# TUDSSL_condenar__Hardware_PCBs_Misc_Apo4.net
KiCad netlist of a schematic drawn in Altium Designer
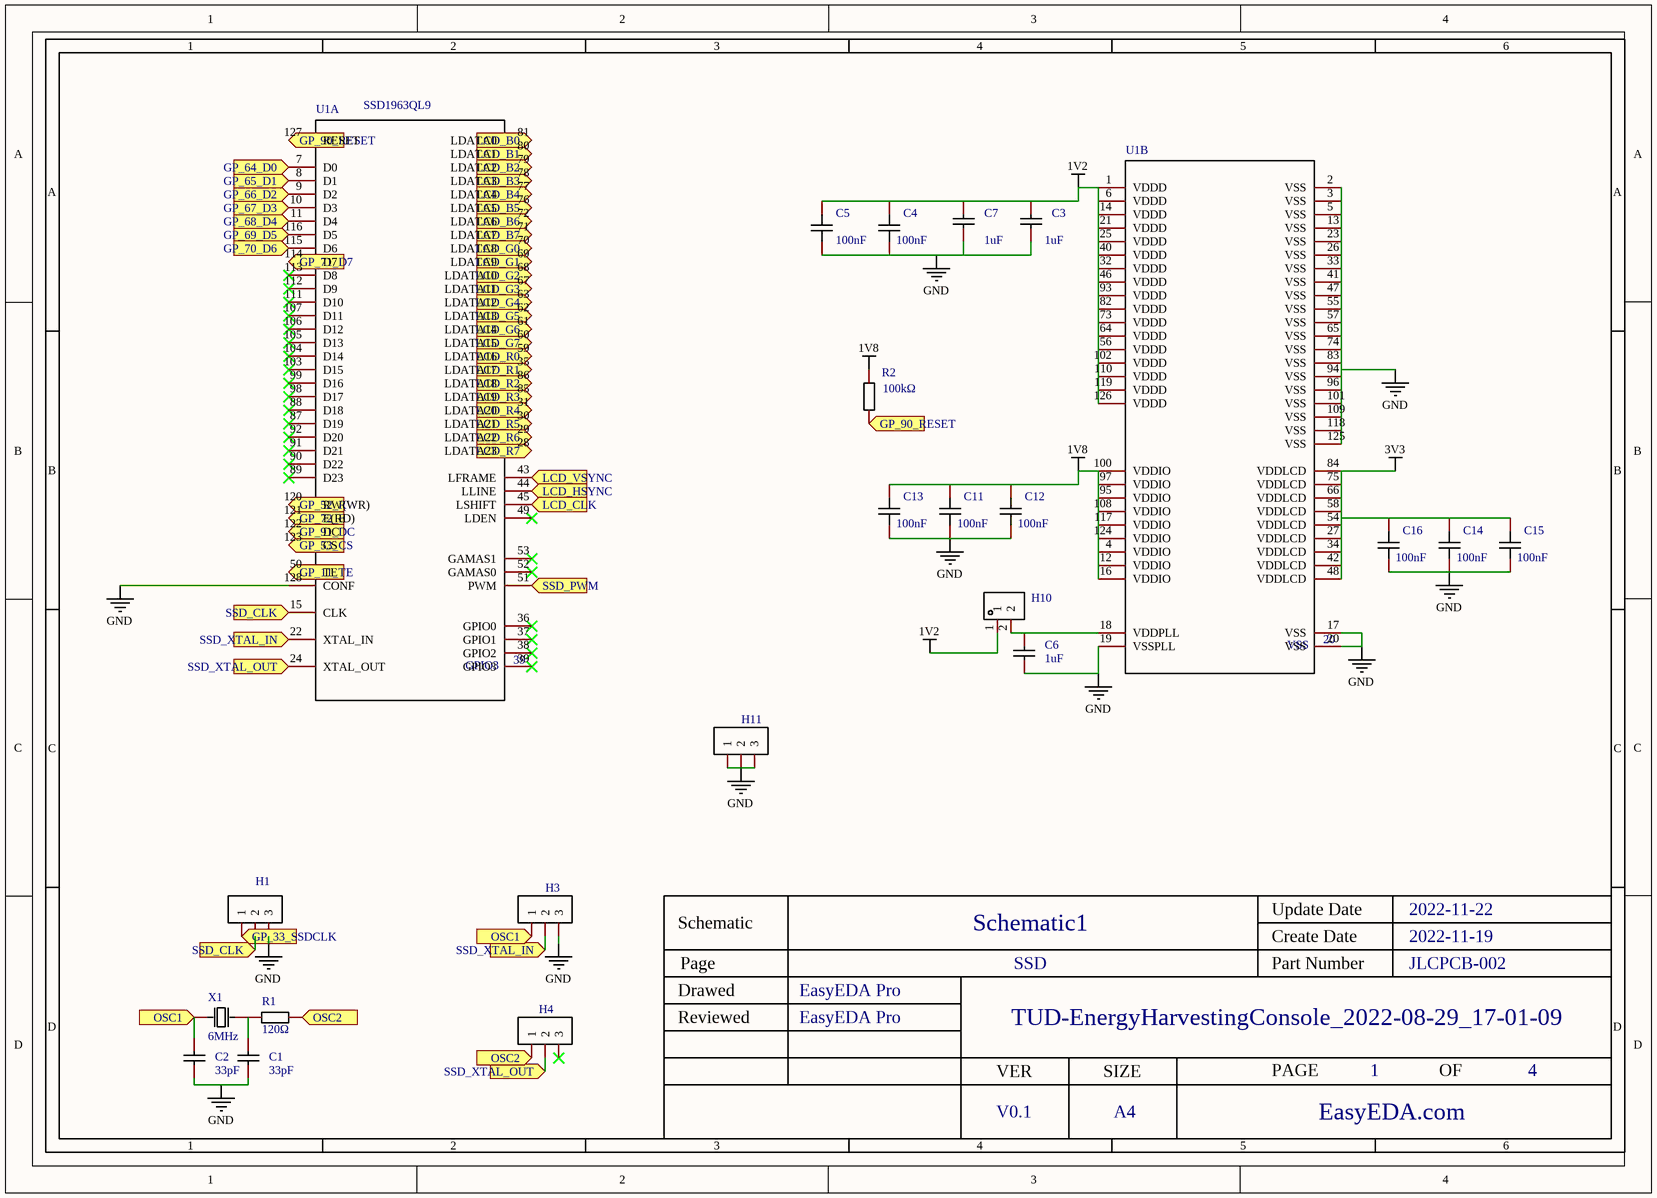
[diagram p0: TUDSSL_condenar__Hardware_PCBs_Misc_Apo4devkit2COM50_Schematic1__4_SSD.schdoc]

(export (version "E")
  (design (tool "Eeschema 10.0.6"))
  (components
    (comp (ref "C1")
      (value "33pF")
      (fields
        (field (name "MANUFACTURER") "YAGEO(国巨)")
        (field (name "MANUFACTURER PART") "CC0805JRNPO9BN330")
        (field (name "TOLERANCE") "±5%")
      )
      (libsource (lib "altium-import") (part "root_1_CC0805JRNPO9BN330_"))
    )
    (comp (ref "C2")
      (value "33pF")
      (fields
        (field (name "MANUFACTURER") "YAGEO(国巨)")
        (field (name "MANUFACTURER PART") "CC0805JRNPO9BN330")
        (field (name "TOLERANCE") "±5%")
      )
      (libsource (lib "altium-import") (part "root_1_CC0805JRNPO9BN330_"))
    )
    (comp (ref "C3")
      (value "1uF")
      (fields
        (field (name "MANUFACTURER") "SAMSUNG(三星)")
        (field (name "MANUFACTURER PART") "CL10A105KB8NNNC")
      )
      (libsource (lib "altium-import") (part "root_1_CL10A105KB8NNNC_"))
    )
    (comp (ref "C4")
      (value "100nF")
      (fields
        (field (name "MANUFACTURER") "YAGEO(国巨)")
        (field (name "MANUFACTURER PART") "CC0603KRX7R9BB104")
        (field (name "TOLERANCE") "±10%")
      )
      (libsource (lib "altium-import") (part "root_1_CC0603KRX7R9BB104_"))
    )
    (comp (ref "C5")
      (value "100nF")
      (fields
        (field (name "MANUFACTURER") "YAGEO(国巨)")
        (field (name "MANUFACTURER PART") "CC0603KRX7R9BB104")
        (field (name "TOLERANCE") "±10%")
      )
      (libsource (lib "altium-import") (part "root_1_CC0603KRX7R9BB104_"))
    )
    (comp (ref "C6")
      (value "1uF")
      (fields
        (field (name "MANUFACTURER") "SAMSUNG(三星)")
        (field (name "MANUFACTURER PART") "CL10A105KB8NNNC")
      )
      (libsource (lib "altium-import") (part "root_1_CL10A105KB8NNNC_"))
    )
    (comp (ref "C7")
      (value "1uF")
      (fields
        (field (name "MANUFACTURER") "SAMSUNG(三星)")
        (field (name "MANUFACTURER PART") "CL10A105KB8NNNC")
      )
      (libsource (lib "altium-import") (part "root_1_CL10A105KB8NNNC_"))
    )
    (comp (ref "C11")
      (value "100nF")
      (fields
        (field (name "MANUFACTURER") "YAGEO(国巨)")
        (field (name "MANUFACTURER PART") "CC0603KRX7R9BB104")
        (field (name "TOLERANCE") "±10%")
      )
      (libsource (lib "altium-import") (part "root_1_CC0603KRX7R9BB104_"))
    )
    (comp (ref "C12")
      (value "100nF")
      (fields
        (field (name "MANUFACTURER") "YAGEO(国巨)")
        (field (name "MANUFACTURER PART") "CC0603KRX7R9BB104")
        (field (name "TOLERANCE") "±10%")
      )
      (libsource (lib "altium-import") (part "root_1_CC0603KRX7R9BB104_"))
    )
    (comp (ref "C13")
      (value "100nF")
      (fields
        (field (name "MANUFACTURER") "YAGEO(国巨)")
        (field (name "MANUFACTURER PART") "CC0603KRX7R9BB104")
        (field (name "TOLERANCE") "±10%")
      )
      (libsource (lib "altium-import") (part "root_1_CC0603KRX7R9BB104_"))
    )
    (comp (ref "C14")
      (value "100nF")
      (fields
        (field (name "MANUFACTURER") "YAGEO(国巨)")
        (field (name "MANUFACTURER PART") "CC0603KRX7R9BB104")
        (field (name "TOLERANCE") "±10%")
      )
      (libsource (lib "altium-import") (part "root_1_CC0603KRX7R9BB104_"))
    )
    (comp (ref "C15")
      (value "100nF")
      (fields
        (field (name "MANUFACTURER") "YAGEO(国巨)")
        (field (name "MANUFACTURER PART") "CC0603KRX7R9BB104")
        (field (name "TOLERANCE") "±10%")
      )
      (libsource (lib "altium-import") (part "root_1_CC0603KRX7R9BB104_"))
    )
    (comp (ref "C16")
      (value "100nF")
      (fields
        (field (name "MANUFACTURER") "YAGEO(国巨)")
        (field (name "MANUFACTURER PART") "CC0603KRX7R9BB104")
        (field (name "TOLERANCE") "±10%")
      )
      (libsource (lib "altium-import") (part "root_1_CC0603KRX7R9BB104_"))
    )
    (comp (ref "H1")
      (value "2.54-1*3P针")
      (fields (field (name "MANUFACTURER") "BOOMELE(博穆精密)"))
      (libsource (lib "altium-import") (part "root_1_2.54-1*3P针_"))
    )
    (comp (ref "H3")
      (value "2.54-1*3P针")
      (fields (field (name "MANUFACTURER") "BOOMELE(博穆精密)"))
      (libsource (lib "altium-import") (part "root_1_2.54-1*3P针_"))
    )
    (comp (ref "H4")
      (value "2.54-1*3P针")
      (fields (field (name "MANUFACTURER") "BOOMELE(博穆精密)"))
      (libsource (lib "altium-import") (part "root_1_2.54-1*3P针_"))
    )
    (comp (ref "H10")
      (value "PZ254V-11-02P")
      (fields (field (name "MANUFACTURER") "XFCN(兴飞)"))
      (libsource (lib "altium-import") (part "root_1_PZ254V-11-02P_"))
    )
    (comp (ref "H11")
      (value "2.54-1*3P针")
      (fields (field (name "MANUFACTURER") "BOOMELE(博穆精密)"))
      (libsource (lib "altium-import") (part "root_1_2.54-1*3P针_"))
    )
    (comp (ref "R1")
      (value "120Ω")
      (fields
        (field (name "MANUFACTURER") "UNI-ROYAL(厚声)")
        (field (name "MANUFACTURER PART") "0603WAF1200T5E")
        (field (name "TOLERANCE") "±1%")
      )
      (libsource (lib "altium-import") (part "root_0_0603WAF1200T5E_"))
    )
    (comp (ref "R2")
      (value "100kΩ")
      (fields
        (field (name "MANUFACTURER") "UNI-ROYAL(厚声)")
        (field (name "MANUFACTURER PART") "0603WAF1003T5E")
        (field (name "TOLERANCE") "±1%")
      )
      (libsource (lib "altium-import") (part "root_1_0603WAF1003T5E_"))
    )
    (comp (ref "U1")
      (value "SSD1963QL9")
      (fields
        (field (name "MANUFACTURER") "SOLOMON(晶门科技)")
        (field (name "NAME") "VSS")
        (field (name "NUMBER") "20")
        (field (name "LCSC PART NAME") "SSD1963QL9")
      )
      (libsource (lib "altium-import") (part "root_0_SSD1963QL9_"))
    )
    (comp (ref "X1")
      (value "6MHz")
      (fields (field (name "MANUFACTURER") "SJK(晶科鑫)") (field (name "MANUFACTURER PART") "6CS06000F20UCG"))
      (libsource (lib "altium-import") (part "root_0_6CS06000F20UCG_"))
    )
  )
  (nets
    (net (code "1") (name "/GP_11_TE") (class "Default")
      (node (ref "U1") (pin "50") (pinfunction "TE_50") (pintype "passive"))
    )
    (net (code "2") (name "/GP_33_SSDCLK") (class "Default")
      (node (ref "H1") (pin "1") (pinfunction "1_1") (pintype "passive"))
    )
    (net (code "3") (name "/GP_52_RW") (class "Default")
      (node (ref "U1") (pin "120") (pinfunction "RW(WR)_120") (pintype "passive"))
    )
    (net (code "4") (name "/GP_53_CS") (class "Default")
      (node (ref "U1") (pin "123") (pinfunction "CS_123") (pintype "passive"))
    )
    (net (code "5") (name "/GP_64_D0") (class "Default")
      (node (ref "U1") (pin "7") (pinfunction "D0_7") (pintype "passive"))
    )
    (net (code "6") (name "/GP_65_D1") (class "Default")
      (node (ref "U1") (pin "8") (pinfunction "D1_8") (pintype "passive"))
    )
    (net (code "7") (name "/GP_66_D2") (class "Default")
      (node (ref "U1") (pin "9") (pinfunction "D2_9") (pintype "passive"))
    )
    (net (code "8") (name "/GP_67_D3") (class "Default")
      (node (ref "U1") (pin "10") (pinfunction "D3_10") (pintype "passive"))
    )
    (net (code "9") (name "/GP_68_D4") (class "Default")
      (node (ref "U1") (pin "11") (pinfunction "D4_11") (pintype "passive"))
    )
    (net (code "10") (name "/GP_69_D5") (class "Default")
      (node (ref "U1") (pin "116") (pinfunction "D5_116") (pintype "passive"))
    )
    (net (code "11") (name "/GP_70_D6") (class "Default")
      (node (ref "U1") (pin "115") (pinfunction "D6_115") (pintype "passive"))
    )
    (net (code "12") (name "/GP_71_D7") (class "Default")
      (node (ref "U1") (pin "114") (pinfunction "D7_114") (pintype "passive"))
    )
    (net (code "13") (name "/GP_72_E") (class "Default")
      (node (ref "U1") (pin "121") (pinfunction "E(RD)_121") (pintype "passive"))
    )
    (net (code "14") (name "/GP_90_RESET") (class "Default")
      (node (ref "R2") (pin "1") (pinfunction "1_1") (pintype "passive"))
      (node (ref "U1") (pin "127") (pinfunction "RESET_127") (pintype "passive"))
    )
    (net (code "15") (name "/GP_91_DC") (class "Default")
      (node (ref "U1") (pin "122") (pinfunction "DC_122") (pintype "passive"))
    )
    (net (code "16") (name "/LCD_B0") (class "Default")
      (node (ref "U1") (pin "81") (pinfunction "LDATA0_81") (pintype "passive"))
    )
    (net (code "17") (name "/LCD_B1") (class "Default")
      (node (ref "U1") (pin "80") (pinfunction "LDATA1_80") (pintype "passive"))
    )
    (net (code "18") (name "/LCD_B2") (class "Default")
      (node (ref "U1") (pin "79") (pinfunction "LDATA2_79") (pintype "passive"))
    )
    (net (code "19") (name "/LCD_B3") (class "Default")
      (node (ref "U1") (pin "78") (pinfunction "LDATA3_78") (pintype "passive"))
    )
    (net (code "20") (name "/LCD_B4") (class "Default")
      (node (ref "U1") (pin "77") (pinfunction "LDATA4_77") (pintype "passive"))
    )
    (net (code "21") (name "/LCD_B5") (class "Default")
      (node (ref "U1") (pin "76") (pinfunction "LDATA5_76") (pintype "passive"))
    )
    (net (code "22") (name "/LCD_B6") (class "Default")
      (node (ref "U1") (pin "72") (pinfunction "LDATA6_72") (pintype "passive"))
    )
    (net (code "23") (name "/LCD_B7") (class "Default")
      (node (ref "U1") (pin "71") (pinfunction "LDATA7_71") (pintype "passive"))
    )
    (net (code "24") (name "/LCD_CLK") (class "Default")
      (node (ref "U1") (pin "45") (pinfunction "LSHIFT_45") (pintype "passive"))
    )
    (net (code "25") (name "/LCD_G0") (class "Default")
      (node (ref "U1") (pin "70") (pinfunction "LDATA8_70") (pintype "passive"))
    )
    (net (code "26") (name "/LCD_G1") (class "Default")
      (node (ref "U1") (pin "69") (pinfunction "LDATA9_69") (pintype "passive"))
    )
    (net (code "27") (name "/LCD_G2") (class "Default")
      (node (ref "U1") (pin "68") (pinfunction "LDATA10_68") (pintype "passive"))
    )
    (net (code "28") (name "/LCD_G3") (class "Default")
      (node (ref "U1") (pin "67") (pinfunction "LDATA11_67") (pintype "passive"))
    )
    (net (code "29") (name "/LCD_G4") (class "Default")
      (node (ref "U1") (pin "63") (pinfunction "LDATA12_63") (pintype "passive"))
    )
    (net (code "30") (name "/LCD_G5") (class "Default")
      (node (ref "U1") (pin "62") (pinfunction "LDATA13_62") (pintype "passive"))
    )
    (net (code "31") (name "/LCD_G6") (class "Default")
      (node (ref "U1") (pin "61") (pinfunction "LDATA14_61") (pintype "passive"))
    )
    (net (code "32") (name "/LCD_G7") (class "Default")
      (node (ref "U1") (pin "60") (pinfunction "LDATA15_60") (pintype "passive"))
    )
    (net (code "33") (name "/LCD_HSYNC") (class "Default")
      (node (ref "U1") (pin "44") (pinfunction "LLINE_44") (pintype "passive"))
    )
    (net (code "34") (name "/LCD_R0") (class "Default")
      (node (ref "U1") (pin "59") (pinfunction "LDATA16_59") (pintype "passive"))
    )
    (net (code "35") (name "/LCD_R1") (class "Default")
      (node (ref "U1") (pin "35") (pinfunction "LDATA17_35") (pintype "passive"))
    )
    (net (code "36") (name "/LCD_R2") (class "Default")
      (node (ref "U1") (pin "86") (pinfunction "LDATA18_86") (pintype "passive"))
    )
    (net (code "37") (name "/LCD_R3") (class "Default")
      (node (ref "U1") (pin "85") (pinfunction "LDATA19_85") (pintype "passive"))
    )
    (net (code "38") (name "/LCD_R4") (class "Default")
      (node (ref "U1") (pin "31") (pinfunction "LDATA20_31") (pintype "passive"))
    )
    (net (code "39") (name "/LCD_R5") (class "Default")
      (node (ref "U1") (pin "30") (pinfunction "LDATA21_30") (pintype "passive"))
    )
    (net (code "40") (name "/LCD_R6") (class "Default")
      (node (ref "U1") (pin "29") (pinfunction "LDATA22_29") (pintype "passive"))
    )
    (net (code "41") (name "/LCD_R7") (class "Default")
      (node (ref "U1") (pin "28") (pinfunction "LDATA23_28") (pintype "passive"))
    )
    (net (code "42") (name "/LCD_VSYNC") (class "Default")
      (node (ref "U1") (pin "43") (pinfunction "LFRAME_43") (pintype "passive"))
    )
    (net (code "43") (name "/OSC1") (class "Default")
      (node (ref "C2") (pin "2") (pinfunction "2_2") (pintype "passive"))
      (node (ref "H3") (pin "1") (pinfunction "1_1") (pintype "passive"))
      (node (ref "X1") (pin "1") (pinfunction "OSC1_1") (pintype "passive"))
    )
    (net (code "44") (name "/OSC2") (class "Default")
      (node (ref "H4") (pin "1") (pinfunction "1_1") (pintype "passive"))
      (node (ref "R1") (pin "2") (pinfunction "2_2") (pintype "passive"))
    )
    (net (code "45") (name "/SSD_CLK") (class "Default")
      (node (ref "H1") (pin "2") (pinfunction "2_2") (pintype "passive"))
      (node (ref "U1") (pin "15") (pinfunction "CLK_15") (pintype "passive"))
    )
    (net (code "46") (name "/SSD_PWM") (class "Default")
      (node (ref "U1") (pin "51") (pinfunction "PWM_51") (pintype "passive"))
    )
    (net (code "47") (name "/SSD_XTAL_IN") (class "Default")
      (node (ref "H3") (pin "2") (pinfunction "2_2") (pintype "passive"))
      (node (ref "U1") (pin "22") (pinfunction "XTAL_IN_22") (pintype "passive"))
    )
    (net (code "48") (name "/SSD_XTAL_OUT") (class "Default")
      (node (ref "H4") (pin "2") (pinfunction "2_2") (pintype "passive"))
      (node (ref "U1") (pin "24") (pinfunction "XTAL_OUT_24") (pintype "passive"))
    )
    (net (code "49") (name "1V2") (class "Default")
      (node (ref "C3") (pin "2") (pinfunction "2_2") (pintype "passive"))
      (node (ref "C4") (pin "2") (pinfunction "2_2") (pintype "passive"))
      (node (ref "C5") (pin "2") (pinfunction "2_2") (pintype "passive"))
      (node (ref "C7") (pin "2") (pinfunction "2_2") (pintype "passive"))
      (node (ref "H10") (pin "1") (pinfunction "1_1") (pintype "passive"))
      (node (ref "U1") (pin "1") (pinfunction "VDDD_1") (pintype "passive"))
      (node (ref "U1") (pin "102") (pinfunction "VDDD_102") (pintype "passive"))
      (node (ref "U1") (pin "110") (pinfunction "VDDD_110") (pintype "passive"))
      (node (ref "U1") (pin "119") (pinfunction "VDDD_119") (pintype "passive"))
      (node (ref "U1") (pin "126") (pinfunction "VDDD_126") (pintype "passive"))
      (node (ref "U1") (pin "14") (pinfunction "VDDD_14") (pintype "passive"))
      (node (ref "U1") (pin "21") (pinfunction "VDDD_21") (pintype "passive"))
      (node (ref "U1") (pin "25") (pinfunction "VDDD_25") (pintype "passive"))
      (node (ref "U1") (pin "32") (pinfunction "VDDD_32") (pintype "passive"))
      (node (ref "U1") (pin "40") (pinfunction "VDDD_40") (pintype "passive"))
      (node (ref "U1") (pin "46") (pinfunction "VDDD_46") (pintype "passive"))
      (node (ref "U1") (pin "56") (pinfunction "VDDD_56") (pintype "passive"))
      (node (ref "U1") (pin "6") (pinfunction "VDDD_6") (pintype "passive"))
      (node (ref "U1") (pin "64") (pinfunction "VDDD_64") (pintype "passive"))
      (node (ref "U1") (pin "73") (pinfunction "VDDD_73") (pintype "passive"))
      (node (ref "U1") (pin "82") (pinfunction "VDDD_82") (pintype "passive"))
      (node (ref "U1") (pin "93") (pinfunction "VDDD_93") (pintype "passive"))
    )
    (net (code "50") (name "1V8") (class "Default")
      (node (ref "C11") (pin "2") (pinfunction "2_2") (pintype "passive"))
      (node (ref "C12") (pin "2") (pinfunction "2_2") (pintype "passive"))
      (node (ref "C13") (pin "2") (pinfunction "2_2") (pintype "passive"))
      (node (ref "R2") (pin "2") (pinfunction "2_2") (pintype "passive"))
      (node (ref "U1") (pin "100") (pinfunction "VDDIO_100") (pintype "passive"))
      (node (ref "U1") (pin "108") (pinfunction "VDDIO_108") (pintype "passive"))
      (node (ref "U1") (pin "117") (pinfunction "VDDIO_117") (pintype "passive"))
      (node (ref "U1") (pin "12") (pinfunction "VDDIO_12") (pintype "passive"))
      (node (ref "U1") (pin "124") (pinfunction "VDDIO_124") (pintype "passive"))
      (node (ref "U1") (pin "16") (pinfunction "VDDIO_16") (pintype "passive"))
      (node (ref "U1") (pin "4") (pinfunction "VDDIO_4") (pintype "passive"))
      (node (ref "U1") (pin "95") (pinfunction "VDDIO_95") (pintype "passive"))
      (node (ref "U1") (pin "97") (pinfunction "VDDIO_97") (pintype "passive"))
    )
    (net (code "51") (name "3V3") (class "Default")
      (node (ref "C14") (pin "2") (pinfunction "2_2") (pintype "passive"))
      (node (ref "C15") (pin "2") (pinfunction "2_2") (pintype "passive"))
      (node (ref "C16") (pin "2") (pinfunction "2_2") (pintype "passive"))
      (node (ref "U1") (pin "27") (pinfunction "VDDLCD_27") (pintype "passive"))
      (node (ref "U1") (pin "34") (pinfunction "VDDLCD_34") (pintype "passive"))
      (node (ref "U1") (pin "42") (pinfunction "VDDLCD_42") (pintype "passive"))
      (node (ref "U1") (pin "48") (pinfunction "VDDLCD_48") (pintype "passive"))
      (node (ref "U1") (pin "54") (pinfunction "VDDLCD_54") (pintype "passive"))
      (node (ref "U1") (pin "58") (pinfunction "VDDLCD_58") (pintype "passive"))
      (node (ref "U1") (pin "66") (pinfunction "VDDLCD_66") (pintype "passive"))
      (node (ref "U1") (pin "75") (pinfunction "VDDLCD_75") (pintype "passive"))
      (node (ref "U1") (pin "84") (pinfunction "VDDLCD_84") (pintype "passive"))
    )
    (net (code "52") (name "GND") (class "Default")
      (node (ref "C1") (pin "1") (pinfunction "1_1") (pintype "passive"))
      (node (ref "C11") (pin "1") (pinfunction "1_1") (pintype "passive"))
      (node (ref "C12") (pin "1") (pinfunction "1_1") (pintype "passive"))
      (node (ref "C13") (pin "1") (pinfunction "1_1") (pintype "passive"))
      (node (ref "C14") (pin "1") (pinfunction "1_1") (pintype "passive"))
      (node (ref "C15") (pin "1") (pinfunction "1_1") (pintype "passive"))
      (node (ref "C16") (pin "1") (pinfunction "1_1") (pintype "passive"))
      (node (ref "C2") (pin "1") (pinfunction "1_1") (pintype "passive"))
      (node (ref "C3") (pin "1") (pinfunction "1_1") (pintype "passive"))
      (node (ref "C4") (pin "1") (pinfunction "1_1") (pintype "passive"))
      (node (ref "C5") (pin "1") (pinfunction "1_1") (pintype "passive"))
      (node (ref "C6") (pin "1") (pinfunction "1_1") (pintype "passive"))
      (node (ref "C7") (pin "1") (pinfunction "1_1") (pintype "passive"))
      (node (ref "H1") (pin "3") (pinfunction "3_3") (pintype "passive"))
      (node (ref "H11") (pin "1") (pinfunction "1_1") (pintype "passive"))
      (node (ref "H11") (pin "2") (pinfunction "2_2") (pintype "passive"))
      (node (ref "H11") (pin "3") (pinfunction "3_3") (pintype "passive"))
      (node (ref "H3") (pin "3") (pinfunction "3_3") (pintype "passive"))
      (node (ref "U1") (pin "101") (pinfunction "VSS_101") (pintype "passive"))
      (node (ref "U1") (pin "109") (pinfunction "VSS_109") (pintype "passive"))
      (node (ref "U1") (pin "118") (pinfunction "VSS_118") (pintype "passive"))
      (node (ref "U1") (pin "125") (pinfunction "VSS_125") (pintype "passive"))
      (node (ref "U1") (pin "128") (pinfunction "CONF_128") (pintype "passive"))
      (node (ref "U1") (pin "13") (pinfunction "VSS_13") (pintype "passive"))
      (node (ref "U1") (pin "17") (pinfunction "VSS_17") (pintype "passive"))
      (node (ref "U1") (pin "19") (pinfunction "VSSPLL_19") (pintype "passive"))
      (node (ref "U1") (pin "2") (pinfunction "VSS_2") (pintype "passive"))
      (node (ref "U1") (pin "20") (pinfunction "VSS_20") (pintype "passive"))
      (node (ref "U1") (pin "23") (pinfunction "VSS_23") (pintype "passive"))
      (node (ref "U1") (pin "26") (pinfunction "VSS_26") (pintype "passive"))
      (node (ref "U1") (pin "3") (pinfunction "VSS_3") (pintype "passive"))
      (node (ref "U1") (pin "33") (pinfunction "VSS_33") (pintype "passive"))
      (node (ref "U1") (pin "41") (pinfunction "VSS_41") (pintype "passive"))
      (node (ref "U1") (pin "47") (pinfunction "VSS_47") (pintype "passive"))
      (node (ref "U1") (pin "5") (pinfunction "VSS_5") (pintype "passive"))
      (node (ref "U1") (pin "55") (pinfunction "VSS_55") (pintype "passive"))
      (node (ref "U1") (pin "57") (pinfunction "VSS_57") (pintype "passive"))
      (node (ref "U1") (pin "65") (pinfunction "VSS_65") (pintype "passive"))
      (node (ref "U1") (pin "74") (pinfunction "VSS_74") (pintype "passive"))
      (node (ref "U1") (pin "83") (pinfunction "VSS_83") (pintype "passive"))
      (node (ref "U1") (pin "94") (pinfunction "VSS_94") (pintype "passive"))
      (node (ref "U1") (pin "96") (pinfunction "VSS_96") (pintype "passive"))
    )
    (net (code "53") (name "Net-(U1B-VDDPLL)") (class "Default")
      (node (ref "C6") (pin "2") (pinfunction "2_2") (pintype "passive"))
      (node (ref "H10") (pin "2") (pinfunction "2_2") (pintype "passive"))
      (node (ref "U1") (pin "18") (pinfunction "VDDPLL_18") (pintype "passive"))
    )
    (net (code "54") (name "Net-(X1-OSC2)") (class "Default")
      (node (ref "C1") (pin "2") (pinfunction "2_2") (pintype "passive"))
      (node (ref "R1") (pin "1") (pinfunction "1_1") (pintype "passive"))
      (node (ref "X1") (pin "2") (pinfunction "OSC2_2") (pintype "passive"))
    )
    (net (code "55") (name "unconnected-(H4-Pad3)") (class "Default")
      (node (ref "H4") (pin "3") (pinfunction "3_3") (pintype "passive+no_connect"))
    )
    (net (code "56") (name "unconnected-(U1A-D8-Pad113)") (class "Default")
      (node (ref "U1") (pin "113") (pinfunction "D8_113") (pintype "passive+no_connect"))
    )
    (net (code "57") (name "unconnected-(U1A-D9-Pad112)") (class "Default")
      (node (ref "U1") (pin "112") (pinfunction "D9_112") (pintype "passive+no_connect"))
    )
    (net (code "58") (name "unconnected-(U1A-D10-Pad111)") (class "Default")
      (node (ref "U1") (pin "111") (pinfunction "D10_111") (pintype "passive+no_connect"))
    )
    (net (code "59") (name "unconnected-(U1A-D11-Pad107)") (class "Default")
      (node (ref "U1") (pin "107") (pinfunction "D11_107") (pintype "passive+no_connect"))
    )
    (net (code "60") (name "unconnected-(U1A-D12-Pad106)") (class "Default")
      (node (ref "U1") (pin "106") (pinfunction "D12_106") (pintype "passive+no_connect"))
    )
    (net (code "61") (name "unconnected-(U1A-D13-Pad105)") (class "Default")
      (node (ref "U1") (pin "105") (pinfunction "D13_105") (pintype "passive+no_connect"))
    )
    (net (code "62") (name "unconnected-(U1A-D14-Pad104)") (class "Default")
      (node (ref "U1") (pin "104") (pinfunction "D14_104") (pintype "passive+no_connect"))
    )
    (net (code "63") (name "unconnected-(U1A-D15-Pad103)") (class "Default")
      (node (ref "U1") (pin "103") (pinfunction "D15_103") (pintype "passive+no_connect"))
    )
    (net (code "64") (name "unconnected-(U1A-D16-Pad99)") (class "Default")
      (node (ref "U1") (pin "99") (pinfunction "D16_99") (pintype "passive+no_connect"))
    )
    (net (code "65") (name "unconnected-(U1A-D17-Pad98)") (class "Default")
      (node (ref "U1") (pin "98") (pinfunction "D17_98") (pintype "passive+no_connect"))
    )
    (net (code "66") (name "unconnected-(U1A-D18-Pad88)") (class "Default")
      (node (ref "U1") (pin "88") (pinfunction "D18_88") (pintype "passive+no_connect"))
    )
    (net (code "67") (name "unconnected-(U1A-D19-Pad87)") (class "Default")
      (node (ref "U1") (pin "87") (pinfunction "D19_87") (pintype "passive+no_connect"))
    )
    (net (code "68") (name "unconnected-(U1A-D20-Pad92)") (class "Default")
      (node (ref "U1") (pin "92") (pinfunction "D20_92") (pintype "passive+no_connect"))
    )
    (net (code "69") (name "unconnected-(U1A-D21-Pad91)") (class "Default")
      (node (ref "U1") (pin "91") (pinfunction "D21_91") (pintype "passive+no_connect"))
    )
    (net (code "70") (name "unconnected-(U1A-D22-Pad90)") (class "Default")
      (node (ref "U1") (pin "90") (pinfunction "D22_90") (pintype "passive+no_connect"))
    )
    (net (code "71") (name "unconnected-(U1A-D23-Pad89)") (class "Default")
      (node (ref "U1") (pin "89") (pinfunction "D23_89") (pintype "passive+no_connect"))
    )
    (net (code "72") (name "unconnected-(U1A-GAMAS0-Pad52)") (class "Default")
      (node (ref "U1") (pin "52") (pinfunction "GAMAS0_52") (pintype "passive+no_connect"))
    )
    (net (code "73") (name "unconnected-(U1A-GAMAS1-Pad53)") (class "Default")
      (node (ref "U1") (pin "53") (pinfunction "GAMAS1_53") (pintype "passive+no_connect"))
    )
    (net (code "74") (name "unconnected-(U1A-GPIO0-Pad36)") (class "Default")
      (node (ref "U1") (pin "36") (pinfunction "GPIO0_36") (pintype "passive+no_connect"))
    )
    (net (code "75") (name "unconnected-(U1A-GPIO1-Pad37)") (class "Default")
      (node (ref "U1") (pin "37") (pinfunction "GPIO1_37") (pintype "passive+no_connect"))
    )
    (net (code "76") (name "unconnected-(U1A-GPIO2-Pad38)") (class "Default")
      (node (ref "U1") (pin "38") (pinfunction "GPIO2_38") (pintype "passive+no_connect"))
    )
    (net (code "77") (name "unconnected-(U1A-GPIO3-Pad39)") (class "Default")
      (node (ref "U1") (pin "39") (pinfunction "GPIO3_39") (pintype "passive+no_connect"))
    )
    (net (code "78") (name "unconnected-(U1A-LDEN-Pad49)") (class "Default")
      (node (ref "U1") (pin "49") (pinfunction "LDEN_49") (pintype "passive+no_connect"))
    )
  )
)
